# Control_board_self_routed.net
KiCad netlist of a schematic drawn in EAGLE
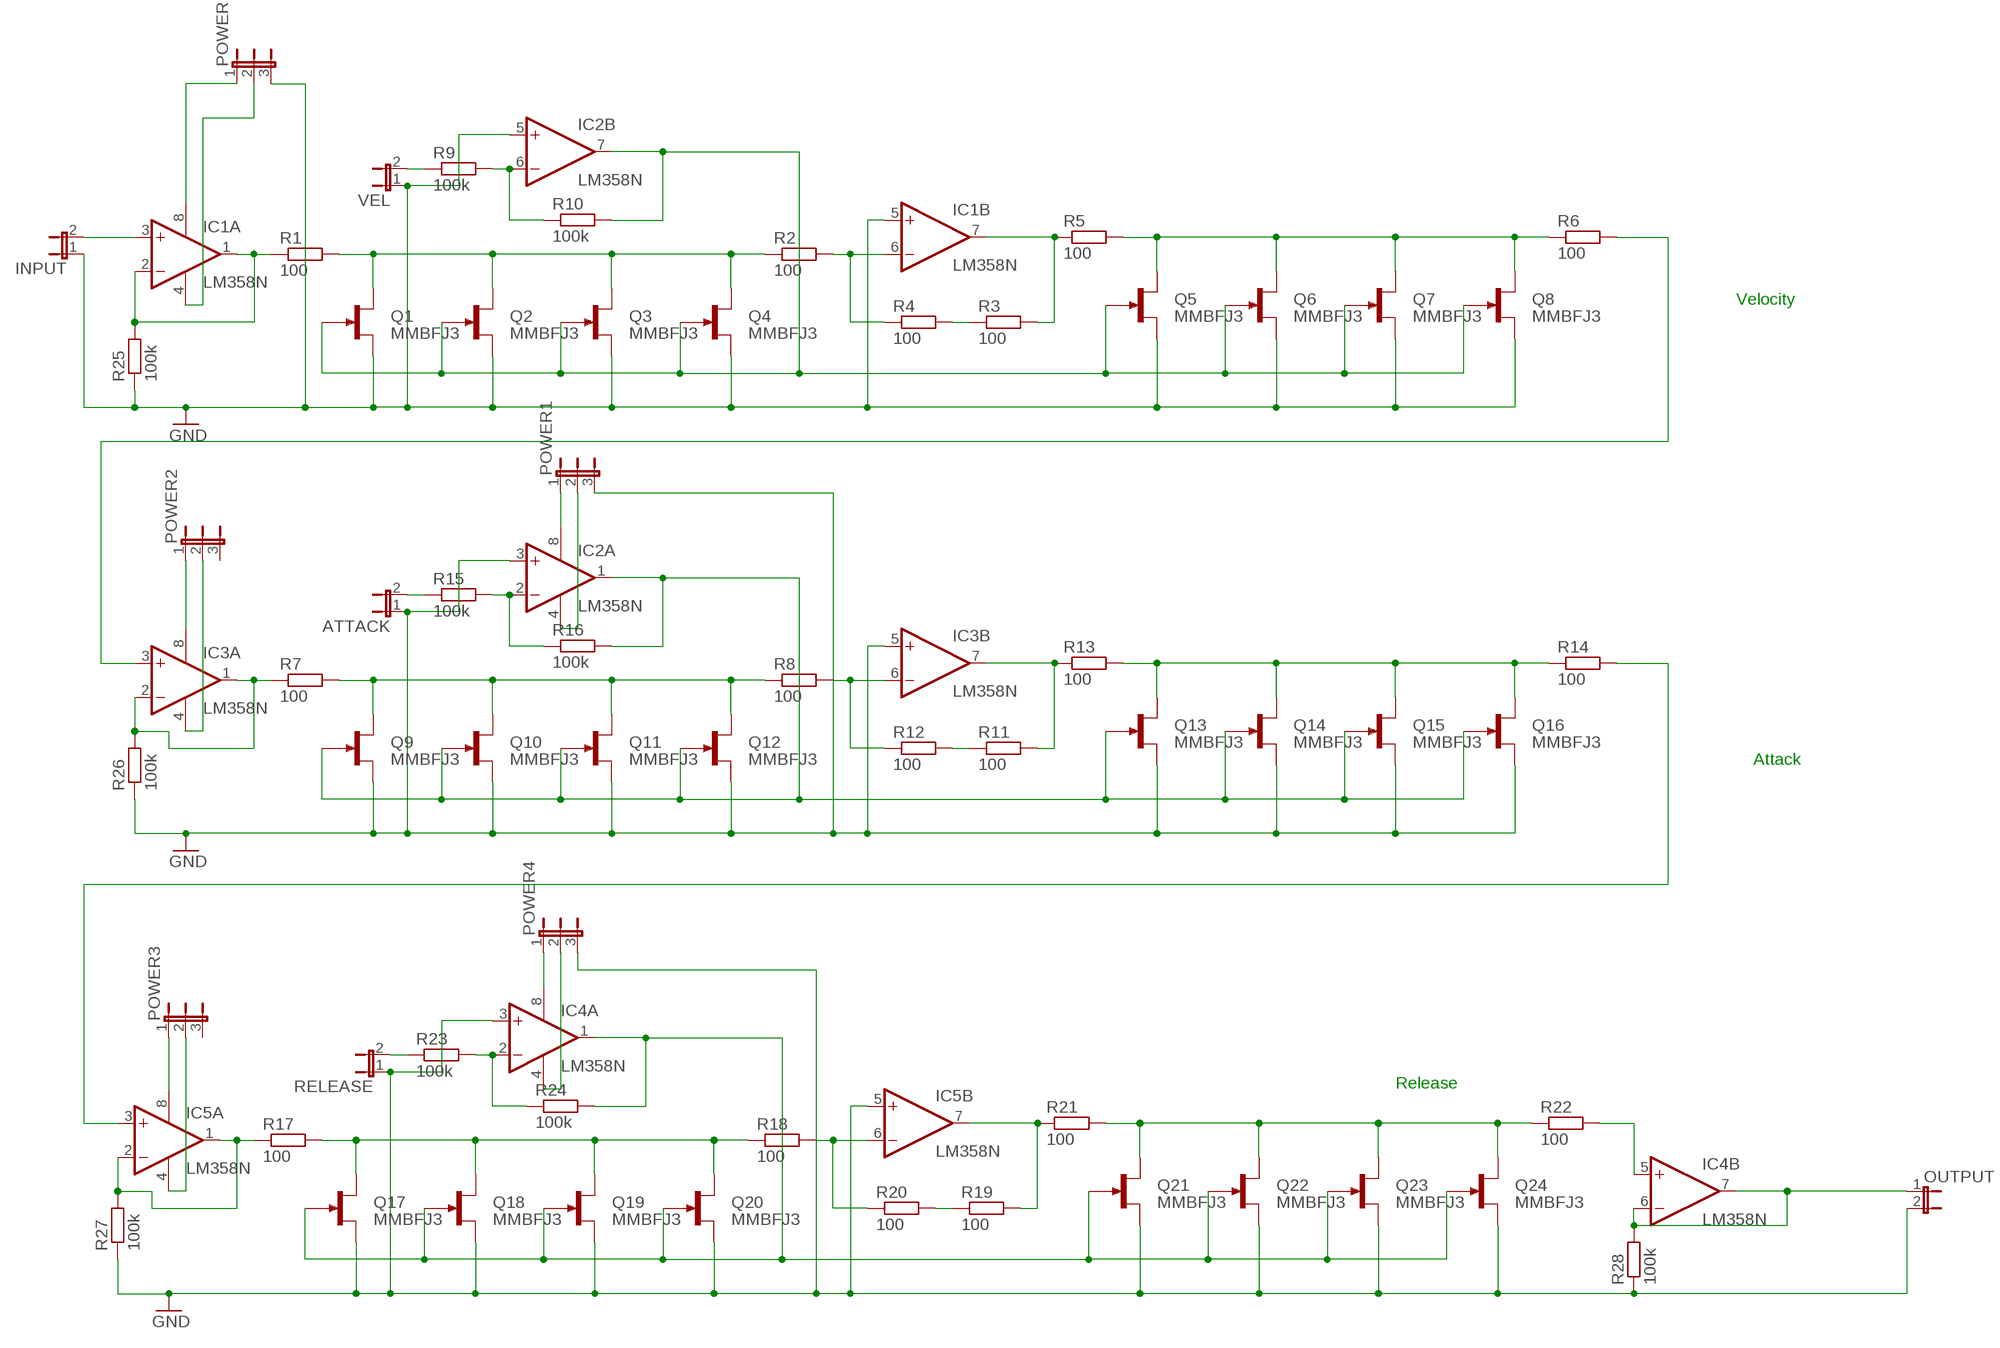
[diagram p0: schematic, sheet 1]

(export (version "E")
  (design (tool "Eeschema 10.0.6"))
  (components
    (comp (ref "ATTACK")
      (value "JP1E")
      (footprint "eagle-import:JP1")
      (libsource (lib "eagle-import") (part "JP1E"))
    )
    (comp (ref "IC1")
      (value "LM358N")
      (footprint "eagle-import:DIL08")
      (libsource (lib "eagle-import") (part "LM358N"))
    )
    (comp (ref "IC2")
      (value "LM358N")
      (footprint "eagle-import:DIL08")
      (libsource (lib "eagle-import") (part "LM358N"))
    )
    (comp (ref "IC3")
      (value "LM358N")
      (footprint "eagle-import:DIL08")
      (libsource (lib "eagle-import") (part "LM358N"))
    )
    (comp (ref "IC4")
      (value "LM358N")
      (footprint "eagle-import:DIL08")
      (libsource (lib "eagle-import") (part "LM358N"))
    )
    (comp (ref "IC5")
      (value "LM358N")
      (footprint "eagle-import:DIL08")
      (libsource (lib "eagle-import") (part "LM358N"))
    )
    (comp (ref "INPUT")
      (value "JP1E")
      (footprint "eagle-import:JP1")
      (libsource (lib "eagle-import") (part "JP1E"))
    )
    (comp (ref "OUTPUT")
      (value "JP1E")
      (footprint "eagle-import:JP1")
      (libsource (lib "eagle-import") (part "JP1E"))
    )
    (comp (ref "POWER")
      (value "JP2E")
      (footprint "eagle-import:JP2")
      (libsource (lib "eagle-import") (part "JP2E"))
    )
    (comp (ref "POWER1")
      (value "JP2E")
      (footprint "eagle-import:JP2")
      (libsource (lib "eagle-import") (part "JP2E"))
    )
    (comp (ref "POWER2")
      (value "JP2E")
      (footprint "eagle-import:JP2")
      (libsource (lib "eagle-import") (part "JP2E"))
    )
    (comp (ref "POWER3")
      (value "JP2E")
      (footprint "eagle-import:JP2")
      (libsource (lib "eagle-import") (part "JP2E"))
    )
    (comp (ref "POWER4")
      (value "JP2E")
      (footprint "eagle-import:JP2")
      (libsource (lib "eagle-import") (part "JP2E"))
    )
    (comp (ref "Q1")
      (value "MMBFJ3")
      (footprint "eagle-import:SOT23")
      (libsource (lib "eagle-import") (part "MMBFJ3"))
    )
    (comp (ref "Q2")
      (value "MMBFJ3")
      (footprint "eagle-import:SOT23")
      (libsource (lib "eagle-import") (part "MMBFJ3"))
    )
    (comp (ref "Q3")
      (value "MMBFJ3")
      (footprint "eagle-import:SOT23")
      (libsource (lib "eagle-import") (part "MMBFJ3"))
    )
    (comp (ref "Q4")
      (value "MMBFJ3")
      (footprint "eagle-import:SOT23")
      (libsource (lib "eagle-import") (part "MMBFJ3"))
    )
    (comp (ref "Q5")
      (value "MMBFJ3")
      (footprint "eagle-import:SOT23")
      (libsource (lib "eagle-import") (part "MMBFJ3"))
    )
    (comp (ref "Q6")
      (value "MMBFJ3")
      (footprint "eagle-import:SOT23")
      (libsource (lib "eagle-import") (part "MMBFJ3"))
    )
    (comp (ref "Q7")
      (value "MMBFJ3")
      (footprint "eagle-import:SOT23")
      (libsource (lib "eagle-import") (part "MMBFJ3"))
    )
    (comp (ref "Q8")
      (value "MMBFJ3")
      (footprint "eagle-import:SOT23")
      (libsource (lib "eagle-import") (part "MMBFJ3"))
    )
    (comp (ref "Q9")
      (value "MMBFJ3")
      (footprint "eagle-import:SOT23")
      (libsource (lib "eagle-import") (part "MMBFJ3"))
    )
    (comp (ref "Q10")
      (value "MMBFJ3")
      (footprint "eagle-import:SOT23")
      (libsource (lib "eagle-import") (part "MMBFJ3"))
    )
    (comp (ref "Q11")
      (value "MMBFJ3")
      (footprint "eagle-import:SOT23")
      (libsource (lib "eagle-import") (part "MMBFJ3"))
    )
    (comp (ref "Q12")
      (value "MMBFJ3")
      (footprint "eagle-import:SOT23")
      (libsource (lib "eagle-import") (part "MMBFJ3"))
    )
    (comp (ref "Q13")
      (value "MMBFJ3")
      (footprint "eagle-import:SOT23")
      (libsource (lib "eagle-import") (part "MMBFJ3"))
    )
    (comp (ref "Q14")
      (value "MMBFJ3")
      (footprint "eagle-import:SOT23")
      (libsource (lib "eagle-import") (part "MMBFJ3"))
    )
    (comp (ref "Q15")
      (value "MMBFJ3")
      (footprint "eagle-import:SOT23")
      (libsource (lib "eagle-import") (part "MMBFJ3"))
    )
    (comp (ref "Q16")
      (value "MMBFJ3")
      (footprint "eagle-import:SOT23")
      (libsource (lib "eagle-import") (part "MMBFJ3"))
    )
    (comp (ref "Q17")
      (value "MMBFJ3")
      (footprint "eagle-import:SOT23")
      (libsource (lib "eagle-import") (part "MMBFJ3"))
    )
    (comp (ref "Q18")
      (value "MMBFJ3")
      (footprint "eagle-import:SOT23")
      (libsource (lib "eagle-import") (part "MMBFJ3"))
    )
    (comp (ref "Q19")
      (value "MMBFJ3")
      (footprint "eagle-import:SOT23")
      (libsource (lib "eagle-import") (part "MMBFJ3"))
    )
    (comp (ref "Q20")
      (value "MMBFJ3")
      (footprint "eagle-import:SOT23")
      (libsource (lib "eagle-import") (part "MMBFJ3"))
    )
    (comp (ref "Q21")
      (value "MMBFJ3")
      (footprint "eagle-import:SOT23")
      (libsource (lib "eagle-import") (part "MMBFJ3"))
    )
    (comp (ref "Q22")
      (value "MMBFJ3")
      (footprint "eagle-import:SOT23")
      (libsource (lib "eagle-import") (part "MMBFJ3"))
    )
    (comp (ref "Q23")
      (value "MMBFJ3")
      (footprint "eagle-import:SOT23")
      (libsource (lib "eagle-import") (part "MMBFJ3"))
    )
    (comp (ref "Q24")
      (value "MMBFJ3")
      (footprint "eagle-import:SOT23")
      (libsource (lib "eagle-import") (part "MMBFJ3"))
    )
    (comp (ref "R1")
      (value "100")
      (footprint "eagle-import:0204_7")
      (libsource (lib "eagle-import") (part "R-EU_0204/7"))
    )
    (comp (ref "R2")
      (value "100")
      (footprint "eagle-import:0204_7")
      (libsource (lib "eagle-import") (part "R-EU_0204/7"))
    )
    (comp (ref "R3")
      (value "100")
      (footprint "eagle-import:0204_7")
      (libsource (lib "eagle-import") (part "R-EU_0204/7"))
    )
    (comp (ref "R4")
      (value "100")
      (footprint "eagle-import:0204_7")
      (libsource (lib "eagle-import") (part "R-EU_0204/7"))
    )
    (comp (ref "R5")
      (value "100")
      (footprint "eagle-import:0204_7")
      (libsource (lib "eagle-import") (part "R-EU_0204/7"))
    )
    (comp (ref "R6")
      (value "100")
      (footprint "eagle-import:0204_7")
      (libsource (lib "eagle-import") (part "R-EU_0204/7"))
    )
    (comp (ref "R7")
      (value "100")
      (footprint "eagle-import:0204_7")
      (libsource (lib "eagle-import") (part "R-EU_0204/7"))
    )
    (comp (ref "R8")
      (value "100")
      (footprint "eagle-import:0204_7")
      (libsource (lib "eagle-import") (part "R-EU_0204/7"))
    )
    (comp (ref "R9")
      (value "100k")
      (footprint "eagle-import:0204_7")
      (libsource (lib "eagle-import") (part "R-EU_0204/7"))
    )
    (comp (ref "R10")
      (value "100k")
      (footprint "eagle-import:0204_7")
      (libsource (lib "eagle-import") (part "R-EU_0204/7"))
    )
    (comp (ref "R11")
      (value "100")
      (footprint "eagle-import:0204_7")
      (libsource (lib "eagle-import") (part "R-EU_0204/7"))
    )
    (comp (ref "R12")
      (value "100")
      (footprint "eagle-import:0204_7")
      (libsource (lib "eagle-import") (part "R-EU_0204/7"))
    )
    (comp (ref "R13")
      (value "100")
      (footprint "eagle-import:0204_7")
      (libsource (lib "eagle-import") (part "R-EU_0204/7"))
    )
    (comp (ref "R14")
      (value "100")
      (footprint "eagle-import:0204_7")
      (libsource (lib "eagle-import") (part "R-EU_0204/7"))
    )
    (comp (ref "R15")
      (value "100k")
      (footprint "eagle-import:0204_7")
      (libsource (lib "eagle-import") (part "R-EU_0204/7"))
    )
    (comp (ref "R16")
      (value "100k")
      (footprint "eagle-import:0204_7")
      (libsource (lib "eagle-import") (part "R-EU_0204/7"))
    )
    (comp (ref "R17")
      (value "100")
      (footprint "eagle-import:0204_7")
      (libsource (lib "eagle-import") (part "R-EU_0204/7"))
    )
    (comp (ref "R18")
      (value "100")
      (footprint "eagle-import:0204_7")
      (libsource (lib "eagle-import") (part "R-EU_0204/7"))
    )
    (comp (ref "R19")
      (value "100")
      (footprint "eagle-import:0204_7")
      (libsource (lib "eagle-import") (part "R-EU_0204/7"))
    )
    (comp (ref "R20")
      (value "100")
      (footprint "eagle-import:0204_7")
      (libsource (lib "eagle-import") (part "R-EU_0204/7"))
    )
    (comp (ref "R21")
      (value "100")
      (footprint "eagle-import:0204_7")
      (libsource (lib "eagle-import") (part "R-EU_0204/7"))
    )
    (comp (ref "R22")
      (value "100")
      (footprint "eagle-import:0204_7")
      (libsource (lib "eagle-import") (part "R-EU_0204/7"))
    )
    (comp (ref "R23")
      (value "100k")
      (footprint "eagle-import:0204_7")
      (libsource (lib "eagle-import") (part "R-EU_0204/7"))
    )
    (comp (ref "R24")
      (value "100k")
      (footprint "eagle-import:0204_7")
      (libsource (lib "eagle-import") (part "R-EU_0204/7"))
    )
    (comp (ref "R25")
      (value "100k")
      (footprint "eagle-import:0204_7")
      (libsource (lib "eagle-import") (part "R-EU_0204/7"))
    )
    (comp (ref "R26")
      (value "100k")
      (footprint "eagle-import:0204_7")
      (libsource (lib "eagle-import") (part "R-EU_0204/7"))
    )
    (comp (ref "R27")
      (value "100k")
      (footprint "eagle-import:0204_7")
      (libsource (lib "eagle-import") (part "R-EU_0204/7"))
    )
    (comp (ref "R28")
      (value "100k")
      (footprint "eagle-import:0204_7")
      (libsource (lib "eagle-import") (part "R-EU_0204/7"))
    )
    (comp (ref "RELEASE")
      (value "JP1E")
      (footprint "eagle-import:JP1")
      (libsource (lib "eagle-import") (part "JP1E"))
    )
    (comp (ref "VEL")
      (value "JP1E")
      (footprint "eagle-import:JP1")
      (libsource (lib "eagle-import") (part "JP1E"))
    )
  )
  (nets
    (net (code "1") (name "GND") (class "Default")
      (node (ref "ATTACK") (pin "1") (pinfunction "1_1") (pintype "passive"))
      (node (ref "IC1") (pin "5") (pinfunction "+IN_5") (pintype "input"))
      (node (ref "IC2") (pin "3") (pinfunction "+IN_3") (pintype "input"))
      (node (ref "IC2") (pin "5") (pinfunction "+IN_5") (pintype "input"))
      (node (ref "IC3") (pin "5") (pinfunction "+IN_5") (pintype "input"))
      (node (ref "IC4") (pin "3") (pinfunction "+IN_3") (pintype "input"))
      (node (ref "IC5") (pin "5") (pinfunction "+IN_5") (pintype "input"))
      (node (ref "INPUT") (pin "1") (pinfunction "1_1") (pintype "passive"))
      (node (ref "OUTPUT") (pin "2") (pinfunction "2_2") (pintype "passive"))
      (node (ref "POWER") (pin "3") (pinfunction "3_3") (pintype "passive"))
      (node (ref "POWER1") (pin "3") (pinfunction "3_3") (pintype "passive"))
      (node (ref "POWER4") (pin "3") (pinfunction "3_3") (pintype "passive"))
      (node (ref "Q1") (pin "2") (pinfunction "S_2") (pintype "passive"))
      (node (ref "Q10") (pin "2") (pinfunction "S_2") (pintype "passive"))
      (node (ref "Q11") (pin "2") (pinfunction "S_2") (pintype "passive"))
      (node (ref "Q12") (pin "2") (pinfunction "S_2") (pintype "passive"))
      (node (ref "Q13") (pin "2") (pinfunction "S_2") (pintype "passive"))
      (node (ref "Q14") (pin "2") (pinfunction "S_2") (pintype "passive"))
      (node (ref "Q15") (pin "2") (pinfunction "S_2") (pintype "passive"))
      (node (ref "Q16") (pin "2") (pinfunction "S_2") (pintype "passive"))
      (node (ref "Q17") (pin "2") (pinfunction "S_2") (pintype "passive"))
      (node (ref "Q18") (pin "2") (pinfunction "S_2") (pintype "passive"))
      (node (ref "Q19") (pin "2") (pinfunction "S_2") (pintype "passive"))
      (node (ref "Q2") (pin "2") (pinfunction "S_2") (pintype "passive"))
      (node (ref "Q20") (pin "2") (pinfunction "S_2") (pintype "passive"))
      (node (ref "Q21") (pin "2") (pinfunction "S_2") (pintype "passive"))
      (node (ref "Q22") (pin "2") (pinfunction "S_2") (pintype "passive"))
      (node (ref "Q23") (pin "2") (pinfunction "S_2") (pintype "passive"))
      (node (ref "Q24") (pin "2") (pinfunction "S_2") (pintype "passive"))
      (node (ref "Q3") (pin "2") (pinfunction "S_2") (pintype "passive"))
      (node (ref "Q4") (pin "2") (pinfunction "S_2") (pintype "passive"))
      (node (ref "Q5") (pin "2") (pinfunction "S_2") (pintype "passive"))
      (node (ref "Q6") (pin "2") (pinfunction "S_2") (pintype "passive"))
      (node (ref "Q7") (pin "2") (pinfunction "S_2") (pintype "passive"))
      (node (ref "Q8") (pin "2") (pinfunction "S_2") (pintype "passive"))
      (node (ref "Q9") (pin "2") (pinfunction "S_2") (pintype "passive"))
      (node (ref "R25") (pin "1") (pinfunction "1_1") (pintype "passive"))
      (node (ref "R26") (pin "1") (pinfunction "1_1") (pintype "passive"))
      (node (ref "R27") (pin "1") (pinfunction "1_1") (pintype "passive"))
      (node (ref "R28") (pin "1") (pinfunction "1_1") (pintype "passive"))
      (node (ref "RELEASE") (pin "1") (pinfunction "1_1") (pintype "passive"))
      (node (ref "VEL") (pin "1") (pinfunction "1_1") (pintype "passive"))
    )
    (net (code "2") (name "Net-(ATTACK-Pad2)") (class "Default")
      (node (ref "ATTACK") (pin "2") (pinfunction "2_2") (pintype "passive"))
      (node (ref "R15") (pin "1") (pinfunction "1_1") (pintype "passive"))
    )
    (net (code "3") (name "Net-(IC1A-+IN)") (class "Default")
      (node (ref "IC1") (pin "3") (pinfunction "+IN_3") (pintype "input"))
      (node (ref "INPUT") (pin "2") (pinfunction "2_2") (pintype "passive"))
    )
    (net (code "4") (name "Net-(IC1A--IN)") (class "Default")
      (node (ref "IC1") (pin "1") (pinfunction "OUT_1") (pintype "output"))
      (node (ref "IC1") (pin "2") (pinfunction "-IN_2") (pintype "input"))
      (node (ref "R1") (pin "1") (pinfunction "1_1") (pintype "passive"))
      (node (ref "R25") (pin "2") (pinfunction "2_2") (pintype "passive"))
    )
    (net (code "5") (name "Net-(IC1B--IN)") (class "Default")
      (node (ref "IC1") (pin "6") (pinfunction "-IN_6") (pintype "input"))
      (node (ref "R2") (pin "2") (pinfunction "2_2") (pintype "passive"))
      (node (ref "R4") (pin "1") (pinfunction "1_1") (pintype "passive"))
    )
    (net (code "6") (name "Net-(IC1B-OUT)") (class "Default")
      (node (ref "IC1") (pin "7") (pinfunction "OUT_7") (pintype "output"))
      (node (ref "R3") (pin "2") (pinfunction "2_2") (pintype "passive"))
      (node (ref "R5") (pin "1") (pinfunction "1_1") (pintype "passive"))
    )
    (net (code "7") (name "Net-(IC1C-V+)") (class "Default")
      (node (ref "IC1") (pin "8") (pinfunction "V+_8") (pintype "power_in"))
      (node (ref "POWER") (pin "1") (pinfunction "1_1") (pintype "passive"))
    )
    (net (code "8") (name "Net-(IC1C-V-)") (class "Default")
      (node (ref "IC1") (pin "4") (pinfunction "V-_4") (pintype "power_in"))
      (node (ref "POWER") (pin "2") (pinfunction "2_2") (pintype "passive"))
    )
    (net (code "9") (name "Net-(IC2A--IN)") (class "Default")
      (node (ref "IC2") (pin "2") (pinfunction "-IN_2") (pintype "input"))
      (node (ref "R15") (pin "2") (pinfunction "2_2") (pintype "passive"))
      (node (ref "R16") (pin "1") (pinfunction "1_1") (pintype "passive"))
    )
    (net (code "10") (name "Net-(IC2A-OUT)") (class "Default")
      (node (ref "IC2") (pin "1") (pinfunction "OUT_1") (pintype "output"))
      (node (ref "Q10") (pin "3") (pinfunction "G_3") (pintype "passive"))
      (node (ref "Q11") (pin "3") (pinfunction "G_3") (pintype "passive"))
      (node (ref "Q12") (pin "3") (pinfunction "G_3") (pintype "passive"))
      (node (ref "Q13") (pin "3") (pinfunction "G_3") (pintype "passive"))
      (node (ref "Q14") (pin "3") (pinfunction "G_3") (pintype "passive"))
      (node (ref "Q15") (pin "3") (pinfunction "G_3") (pintype "passive"))
      (node (ref "Q16") (pin "3") (pinfunction "G_3") (pintype "passive"))
      (node (ref "Q9") (pin "3") (pinfunction "G_3") (pintype "passive"))
      (node (ref "R16") (pin "2") (pinfunction "2_2") (pintype "passive"))
    )
    (net (code "11") (name "Net-(IC2B--IN)") (class "Default")
      (node (ref "IC2") (pin "6") (pinfunction "-IN_6") (pintype "input"))
      (node (ref "R10") (pin "1") (pinfunction "1_1") (pintype "passive"))
      (node (ref "R9") (pin "2") (pinfunction "2_2") (pintype "passive"))
    )
    (net (code "12") (name "Net-(IC2B-OUT)") (class "Default")
      (node (ref "IC2") (pin "7") (pinfunction "OUT_7") (pintype "output"))
      (node (ref "Q1") (pin "3") (pinfunction "G_3") (pintype "passive"))
      (node (ref "Q2") (pin "3") (pinfunction "G_3") (pintype "passive"))
      (node (ref "Q3") (pin "3") (pinfunction "G_3") (pintype "passive"))
      (node (ref "Q4") (pin "3") (pinfunction "G_3") (pintype "passive"))
      (node (ref "Q5") (pin "3") (pinfunction "G_3") (pintype "passive"))
      (node (ref "Q6") (pin "3") (pinfunction "G_3") (pintype "passive"))
      (node (ref "Q7") (pin "3") (pinfunction "G_3") (pintype "passive"))
      (node (ref "Q8") (pin "3") (pinfunction "G_3") (pintype "passive"))
      (node (ref "R10") (pin "2") (pinfunction "2_2") (pintype "passive"))
    )
    (net (code "13") (name "Net-(IC2C-V+)") (class "Default")
      (node (ref "IC2") (pin "8") (pinfunction "V+_8") (pintype "power_in"))
      (node (ref "POWER1") (pin "1") (pinfunction "1_1") (pintype "passive"))
    )
    (net (code "14") (name "Net-(IC2C-V-)") (class "Default")
      (node (ref "IC2") (pin "4") (pinfunction "V-_4") (pintype "power_in"))
      (node (ref "POWER1") (pin "2") (pinfunction "2_2") (pintype "passive"))
    )
    (net (code "15") (name "Net-(IC3A-+IN)") (class "Default")
      (node (ref "IC3") (pin "3") (pinfunction "+IN_3") (pintype "input"))
      (node (ref "R6") (pin "2") (pinfunction "2_2") (pintype "passive"))
    )
    (net (code "16") (name "Net-(IC3A--IN)") (class "Default")
      (node (ref "IC3") (pin "1") (pinfunction "OUT_1") (pintype "output"))
      (node (ref "IC3") (pin "2") (pinfunction "-IN_2") (pintype "input"))
      (node (ref "R26") (pin "2") (pinfunction "2_2") (pintype "passive"))
      (node (ref "R7") (pin "1") (pinfunction "1_1") (pintype "passive"))
    )
    (net (code "17") (name "Net-(IC3B--IN)") (class "Default")
      (node (ref "IC3") (pin "6") (pinfunction "-IN_6") (pintype "input"))
      (node (ref "R12") (pin "1") (pinfunction "1_1") (pintype "passive"))
      (node (ref "R8") (pin "2") (pinfunction "2_2") (pintype "passive"))
    )
    (net (code "18") (name "Net-(IC3B-OUT)") (class "Default")
      (node (ref "IC3") (pin "7") (pinfunction "OUT_7") (pintype "output"))
      (node (ref "R11") (pin "2") (pinfunction "2_2") (pintype "passive"))
      (node (ref "R13") (pin "1") (pinfunction "1_1") (pintype "passive"))
    )
    (net (code "19") (name "Net-(IC3C-V+)") (class "Default")
      (node (ref "IC3") (pin "8") (pinfunction "V+_8") (pintype "power_in"))
      (node (ref "POWER2") (pin "1") (pinfunction "1_1") (pintype "passive"))
    )
    (net (code "20") (name "Net-(IC3C-V-)") (class "Default")
      (node (ref "IC3") (pin "4") (pinfunction "V-_4") (pintype "power_in"))
      (node (ref "POWER2") (pin "2") (pinfunction "2_2") (pintype "passive"))
    )
    (net (code "21") (name "Net-(IC4A--IN)") (class "Default")
      (node (ref "IC4") (pin "2") (pinfunction "-IN_2") (pintype "input"))
      (node (ref "R23") (pin "2") (pinfunction "2_2") (pintype "passive"))
      (node (ref "R24") (pin "1") (pinfunction "1_1") (pintype "passive"))
    )
    (net (code "22") (name "Net-(IC4A-OUT)") (class "Default")
      (node (ref "IC4") (pin "1") (pinfunction "OUT_1") (pintype "output"))
      (node (ref "Q17") (pin "3") (pinfunction "G_3") (pintype "passive"))
      (node (ref "Q18") (pin "3") (pinfunction "G_3") (pintype "passive"))
      (node (ref "Q19") (pin "3") (pinfunction "G_3") (pintype "passive"))
      (node (ref "Q20") (pin "3") (pinfunction "G_3") (pintype "passive"))
      (node (ref "Q21") (pin "3") (pinfunction "G_3") (pintype "passive"))
      (node (ref "Q22") (pin "3") (pinfunction "G_3") (pintype "passive"))
      (node (ref "Q23") (pin "3") (pinfunction "G_3") (pintype "passive"))
      (node (ref "Q24") (pin "3") (pinfunction "G_3") (pintype "passive"))
      (node (ref "R24") (pin "2") (pinfunction "2_2") (pintype "passive"))
    )
    (net (code "23") (name "Net-(IC4B-+IN)") (class "Default")
      (node (ref "IC4") (pin "5") (pinfunction "+IN_5") (pintype "input"))
      (node (ref "R22") (pin "2") (pinfunction "2_2") (pintype "passive"))
    )
    (net (code "24") (name "Net-(IC4B--IN)") (class "Default")
      (node (ref "IC4") (pin "6") (pinfunction "-IN_6") (pintype "input"))
      (node (ref "IC4") (pin "7") (pinfunction "OUT_7") (pintype "output"))
      (node (ref "OUTPUT") (pin "1") (pinfunction "1_1") (pintype "passive"))
      (node (ref "R28") (pin "2") (pinfunction "2_2") (pintype "passive"))
    )
    (net (code "25") (name "Net-(IC4C-V+)") (class "Default")
      (node (ref "IC4") (pin "8") (pinfunction "V+_8") (pintype "power_in"))
      (node (ref "POWER4") (pin "1") (pinfunction "1_1") (pintype "passive"))
    )
    (net (code "26") (name "Net-(IC4C-V-)") (class "Default")
      (node (ref "IC4") (pin "4") (pinfunction "V-_4") (pintype "power_in"))
      (node (ref "POWER4") (pin "2") (pinfunction "2_2") (pintype "passive"))
    )
    (net (code "27") (name "Net-(IC5A-+IN)") (class "Default")
      (node (ref "IC5") (pin "3") (pinfunction "+IN_3") (pintype "input"))
      (node (ref "R14") (pin "2") (pinfunction "2_2") (pintype "passive"))
    )
    (net (code "28") (name "Net-(IC5A--IN)") (class "Default")
      (node (ref "IC5") (pin "1") (pinfunction "OUT_1") (pintype "output"))
      (node (ref "IC5") (pin "2") (pinfunction "-IN_2") (pintype "input"))
      (node (ref "R17") (pin "1") (pinfunction "1_1") (pintype "passive"))
      (node (ref "R27") (pin "2") (pinfunction "2_2") (pintype "passive"))
    )
    (net (code "29") (name "Net-(IC5B--IN)") (class "Default")
      (node (ref "IC5") (pin "6") (pinfunction "-IN_6") (pintype "input"))
      (node (ref "R18") (pin "2") (pinfunction "2_2") (pintype "passive"))
      (node (ref "R20") (pin "1") (pinfunction "1_1") (pintype "passive"))
    )
    (net (code "30") (name "Net-(IC5B-OUT)") (class "Default")
      (node (ref "IC5") (pin "7") (pinfunction "OUT_7") (pintype "output"))
      (node (ref "R19") (pin "2") (pinfunction "2_2") (pintype "passive"))
      (node (ref "R21") (pin "1") (pinfunction "1_1") (pintype "passive"))
    )
    (net (code "31") (name "Net-(IC5C-V+)") (class "Default")
      (node (ref "IC5") (pin "8") (pinfunction "V+_8") (pintype "power_in"))
      (node (ref "POWER3") (pin "1") (pinfunction "1_1") (pintype "passive"))
    )
    (net (code "32") (name "Net-(IC5C-V-)") (class "Default")
      (node (ref "IC5") (pin "4") (pinfunction "V-_4") (pintype "power_in"))
      (node (ref "POWER3") (pin "2") (pinfunction "2_2") (pintype "passive"))
    )
    (net (code "33") (name "Net-(Q1-D)") (class "Default")
      (node (ref "Q1") (pin "1") (pinfunction "D_1") (pintype "passive"))
      (node (ref "Q2") (pin "1") (pinfunction "D_1") (pintype "passive"))
      (node (ref "Q3") (pin "1") (pinfunction "D_1") (pintype "passive"))
      (node (ref "Q4") (pin "1") (pinfunction "D_1") (pintype "passive"))
      (node (ref "R1") (pin "2") (pinfunction "2_2") (pintype "passive"))
      (node (ref "R2") (pin "1") (pinfunction "1_1") (pintype "passive"))
    )
    (net (code "34") (name "Net-(Q5-D)") (class "Default")
      (node (ref "Q5") (pin "1") (pinfunction "D_1") (pintype "passive"))
      (node (ref "Q6") (pin "1") (pinfunction "D_1") (pintype "passive"))
      (node (ref "Q7") (pin "1") (pinfunction "D_1") (pintype "passive"))
      (node (ref "Q8") (pin "1") (pinfunction "D_1") (pintype "passive"))
      (node (ref "R5") (pin "2") (pinfunction "2_2") (pintype "passive"))
      (node (ref "R6") (pin "1") (pinfunction "1_1") (pintype "passive"))
    )
    (net (code "35") (name "Net-(Q10-D)") (class "Default")
      (node (ref "Q10") (pin "1") (pinfunction "D_1") (pintype "passive"))
      (node (ref "Q11") (pin "1") (pinfunction "D_1") (pintype "passive"))
      (node (ref "Q12") (pin "1") (pinfunction "D_1") (pintype "passive"))
      (node (ref "Q9") (pin "1") (pinfunction "D_1") (pintype "passive"))
      (node (ref "R7") (pin "2") (pinfunction "2_2") (pintype "passive"))
      (node (ref "R8") (pin "1") (pinfunction "1_1") (pintype "passive"))
    )
    (net (code "36") (name "Net-(Q13-D)") (class "Default")
      (node (ref "Q13") (pin "1") (pinfunction "D_1") (pintype "passive"))
      (node (ref "Q14") (pin "1") (pinfunction "D_1") (pintype "passive"))
      (node (ref "Q15") (pin "1") (pinfunction "D_1") (pintype "passive"))
      (node (ref "Q16") (pin "1") (pinfunction "D_1") (pintype "passive"))
      (node (ref "R13") (pin "2") (pinfunction "2_2") (pintype "passive"))
      (node (ref "R14") (pin "1") (pinfunction "1_1") (pintype "passive"))
    )
    (net (code "37") (name "Net-(Q17-D)") (class "Default")
      (node (ref "Q17") (pin "1") (pinfunction "D_1") (pintype "passive"))
      (node (ref "Q18") (pin "1") (pinfunction "D_1") (pintype "passive"))
      (node (ref "Q19") (pin "1") (pinfunction "D_1") (pintype "passive"))
      (node (ref "Q20") (pin "1") (pinfunction "D_1") (pintype "passive"))
      (node (ref "R17") (pin "2") (pinfunction "2_2") (pintype "passive"))
      (node (ref "R18") (pin "1") (pinfunction "1_1") (pintype "passive"))
    )
    (net (code "38") (name "Net-(Q21-D)") (class "Default")
      (node (ref "Q21") (pin "1") (pinfunction "D_1") (pintype "passive"))
      (node (ref "Q22") (pin "1") (pinfunction "D_1") (pintype "passive"))
      (node (ref "Q23") (pin "1") (pinfunction "D_1") (pintype "passive"))
      (node (ref "Q24") (pin "1") (pinfunction "D_1") (pintype "passive"))
      (node (ref "R21") (pin "2") (pinfunction "2_2") (pintype "passive"))
      (node (ref "R22") (pin "1") (pinfunction "1_1") (pintype "passive"))
    )
    (net (code "39") (name "Net-(R3-Pad1)") (class "Default")
      (node (ref "R3") (pin "1") (pinfunction "1_1") (pintype "passive"))
      (node (ref "R4") (pin "2") (pinfunction "2_2") (pintype "passive"))
    )
    (net (code "40") (name "Net-(R9-Pad1)") (class "Default")
      (node (ref "R9") (pin "1") (pinfunction "1_1") (pintype "passive"))
      (node (ref "VEL") (pin "2") (pinfunction "2_2") (pintype "passive"))
    )
    (net (code "41") (name "Net-(R11-Pad1)") (class "Default")
      (node (ref "R11") (pin "1") (pinfunction "1_1") (pintype "passive"))
      (node (ref "R12") (pin "2") (pinfunction "2_2") (pintype "passive"))
    )
    (net (code "42") (name "Net-(R19-Pad1)") (class "Default")
      (node (ref "R19") (pin "1") (pinfunction "1_1") (pintype "passive"))
      (node (ref "R20") (pin "2") (pinfunction "2_2") (pintype "passive"))
    )
    (net (code "43") (name "Net-(R23-Pad1)") (class "Default")
      (node (ref "R23") (pin "1") (pinfunction "1_1") (pintype "passive"))
      (node (ref "RELEASE") (pin "2") (pinfunction "2_2") (pintype "passive"))
    )
    (net (code "44") (name "unconnected-(POWER2-Pad3)") (class "Default")
      (node (ref "POWER2") (pin "3") (pinfunction "3_3") (pintype "passive"))
    )
    (net (code "45") (name "unconnected-(POWER3-Pad3)") (class "Default")
      (node (ref "POWER3") (pin "3") (pinfunction "3_3") (pintype "passive"))
    )
  )
)
